# ARM_EURO_Platine3.net
KiCad netlist of a schematic drawn in Altium Designer
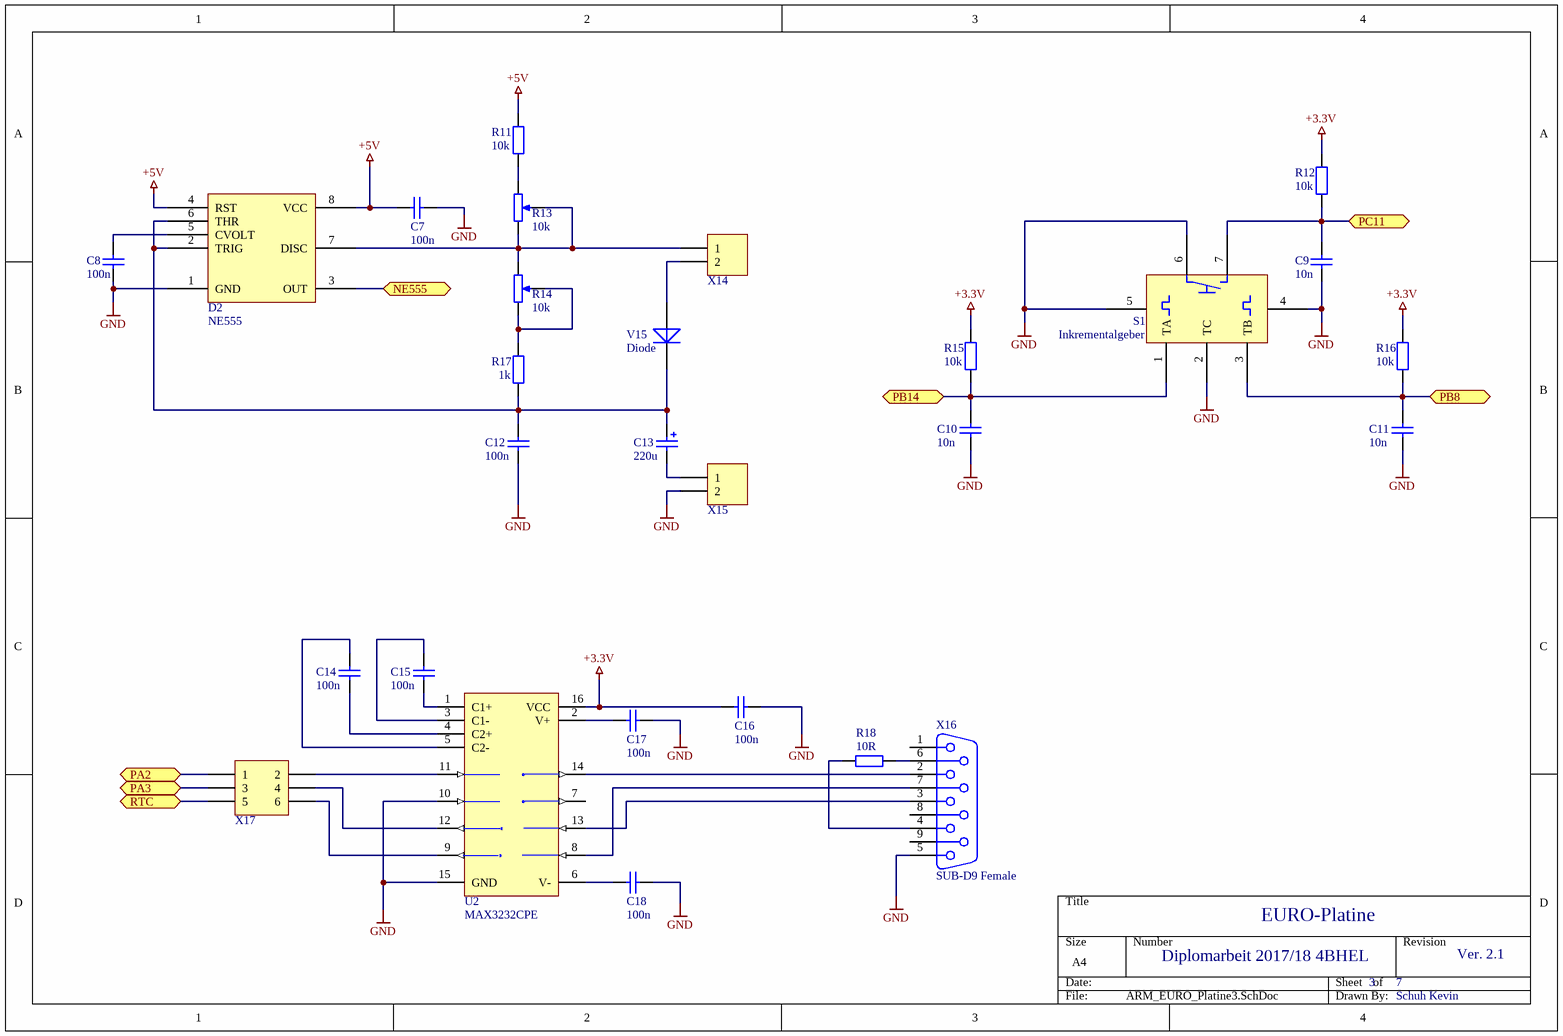
[diagram p0: ARM_EURO_Platine3.SchDoc]

(export (version "E")
  (design (tool "Eeschema 10.0.6"))
  (components
    (comp (ref "C7")
      (value "100n")
      (footprint "0805_CAP")
      (description "Capacitor_SMD")
      (fields (field (name "Comment") "Cap_Keramik_SMD") (field (name "PUBLISHER") "Altium Limited"))
      (libsource (lib "ARM_Libary_EURO") (part "Cap_Keramik_SMD"))
    )
    (comp (ref "C8")
      (value "100n")
      (footprint "0805_CAP")
      (description "Capacitor_SMD")
      (fields (field (name "Comment") "Cap_Keramik_SMD") (field (name "PUBLISHER") "Altium Limited"))
      (libsource (lib "ARM_Libary_EURO") (part "Cap_Keramik_SMD"))
    )
    (comp (ref "C9")
      (value "10n")
      (footprint "0805_CAP")
      (description "Capacitor_SMD")
      (fields (field (name "Comment") "Cap_Keramik_SMD") (field (name "PUBLISHER") "Altium Limited"))
      (libsource (lib "ARM_Libary_EURO") (part "Cap_Keramik_SMD"))
    )
    (comp (ref "C10")
      (value "10n")
      (footprint "0805_CAP")
      (description "Capacitor_SMD")
      (fields (field (name "Comment") "Cap_Keramik_SMD") (field (name "PUBLISHER") "Altium Limited"))
      (libsource (lib "ARM_Libary_EURO") (part "Cap_Keramik_SMD"))
    )
    (comp (ref "C11")
      (value "10n")
      (footprint "0805_CAP")
      (description "Capacitor_SMD")
      (fields (field (name "Comment") "Cap_Keramik_SMD") (field (name "PUBLISHER") "Altium Limited"))
      (libsource (lib "ARM_Libary_EURO") (part "Cap_Keramik_SMD"))
    )
    (comp (ref "C12")
      (value "100n")
      (footprint "0805_CAP")
      (description "Capacitor_SMD")
      (fields (field (name "Comment") "Cap_Keramik_SMD") (field (name "PUBLISHER") "Altium Limited"))
      (libsource (lib "ARM_Libary_EURO") (part "Cap_Keramik_SMD"))
    )
    (comp (ref "C13")
      (value "220u")
      (footprint "100µF_16V_Kondensator")
      (description "Polarized Capacitor SMD")
      (fields (field (name "Comment") "Cap_Pol_SMD") (field (name "PUBLISHER") "Altium Limited"))
      (libsource (lib "ARM_Libary_EURO") (part "Cap_Pol_SMD"))
    )
    (comp (ref "C14")
      (value "100n")
      (footprint "0805_CAP")
      (description "Capacitor_SMD")
      (fields (field (name "Comment") "Cap_Keramik_SMD") (field (name "PUBLISHER") "Altium Limited"))
      (libsource (lib "ARM_Libary_EURO") (part "Cap_Keramik_SMD"))
    )
    (comp (ref "C15")
      (value "100n")
      (footprint "0805_CAP")
      (description "Capacitor_SMD")
      (fields (field (name "Comment") "Cap_Keramik_SMD") (field (name "PUBLISHER") "Altium Limited"))
      (libsource (lib "ARM_Libary_EURO") (part "Cap_Keramik_SMD"))
    )
    (comp (ref "C16")
      (value "100n")
      (footprint "0805_CAP")
      (description "Capacitor_SMD")
      (fields (field (name "Comment") "Cap_Keramik_SMD") (field (name "PUBLISHER") "Altium Limited"))
      (libsource (lib "ARM_Libary_EURO") (part "Cap_Keramik_SMD"))
    )
    (comp (ref "C17")
      (value "100n")
      (footprint "0805_CAP")
      (description "Capacitor_SMD")
      (fields (field (name "Comment") "Cap_Keramik_SMD") (field (name "PUBLISHER") "Altium Limited"))
      (libsource (lib "ARM_Libary_EURO") (part "Cap_Keramik_SMD"))
    )
    (comp (ref "C18")
      (value "100n")
      (footprint "0805_CAP")
      (description "Capacitor_SMD")
      (fields (field (name "Comment") "Cap_Keramik_SMD") (field (name "PUBLISHER") "Altium Limited"))
      (libsource (lib "ARM_Libary_EURO") (part "Cap_Keramik_SMD"))
    )
    (comp (ref "D2") (value "NE555") (footprint "PDIP8") (libsource (lib "ARM_Libary_EURO") (part "NE555")))
    (comp (ref "R11")
      (value "10k")
      (footprint "0805_Res")
      (description "Resistor")
      (fields (field (name "Comment") "Res_SMD") (field (name "PUBLISHER") "Altium Limited"))
      (libsource (lib "ARM_Libary_EURO") (part "Res_SMD"))
    )
    (comp (ref "R12")
      (value "10k")
      (footprint "0805_Res")
      (description "Resistor")
      (fields (field (name "Comment") "Res_SMD") (field (name "PUBLISHER") "Altium Limited"))
      (libsource (lib "ARM_Libary_EURO") (part "Res_SMD"))
    )
    (comp (ref "R13")
      (value "10k")
      (footprint "Potentiometer")
      (description "Potentiometer")
      (fields (field (name "Comment") "RPot") (field (name "PUBLISHER") "Altium Limited"))
      (libsource (lib "ARM_Libary_EURO") (part "RPot"))
    )
    (comp (ref "R14")
      (value "10k")
      (footprint "Potentiometer")
      (description "Potentiometer")
      (fields (field (name "Comment") "RPot") (field (name "PUBLISHER") "Altium Limited"))
      (libsource (lib "ARM_Libary_EURO") (part "RPot"))
    )
    (comp (ref "R15")
      (value "10k")
      (footprint "0805_Res")
      (description "Resistor")
      (fields (field (name "Comment") "Res_SMD") (field (name "PUBLISHER") "Altium Limited"))
      (libsource (lib "ARM_Libary_EURO") (part "Res_SMD"))
    )
    (comp (ref "R16")
      (value "10k")
      (footprint "0805_Res")
      (description "Resistor")
      (fields (field (name "Comment") "Res_SMD") (field (name "PUBLISHER") "Altium Limited"))
      (libsource (lib "ARM_Libary_EURO") (part "Res_SMD"))
    )
    (comp (ref "R17")
      (value "1k")
      (footprint "0805_Res")
      (description "Resistor")
      (fields (field (name "Comment") "Res_SMD") (field (name "PUBLISHER") "Altium Limited"))
      (libsource (lib "ARM_Libary_EURO") (part "Res_SMD"))
    )
    (comp (ref "R18")
      (value "10R")
      (footprint "0805_Res")
      (description "Resistor")
      (fields (field (name "Comment") "Res_SMD") (field (name "PUBLISHER") "Altium Limited"))
      (libsource (lib "") (part "Res_SMD_1"))
    )
    (comp (ref "S1")
      (value "Inkrementalgeber")
      (footprint "Inkrementalgeber")
      (libsource (lib "ARM_Libary_EURO") (part "Inkrementalgeber"))
    )
    (comp (ref "U2")
      (value "MAX3232CPE")
      (footprint "DIP_16")
      (description "3.0V TO 5.5V, Low-Power, up to 1Mbps, True RS-232 Transceiver Using Four 0.1µF External Capacitor")
      (fields (field (name "PUBLISHER") "Altium Limited"))
      (libsource (lib "ARM_Libary_EURO") (part "MAX3232CPE"))
    )
    (comp (ref "V15")
      (value "Diode")
      (footprint "Diode")
      (description "Schottky Diode")
      (fields (field (name "PUBLISHER") "Altium Limited"))
      (libsource (lib "ARM_Libary_EURO") (part "Diode"))
    )
    (comp (ref "X14")
      (value "Header")
      (footprint "HDR1X2")
      (description "Header, 2-Pin")
      (fields (field (name "PUBLISHER") "Altium Limited"))
      (libsource (lib "ARM_Libary_EURO") (part "Header_2"))
    )
    (comp (ref "X15")
      (value "Header")
      (footprint "HDR1X2")
      (description "Header, 2-Pin")
      (fields (field (name "PUBLISHER") "Altium Limited"))
      (libsource (lib "ARM_Libary_EURO") (part "Header_2"))
    )
    (comp (ref "X16")
      (value "SUB-D9 Female")
      (footprint "SUBD_9")
      (fields (field (name "PUBLISHER") "Altium Limited"))
      (libsource (lib "ARM_Libary_EURO") (part "SUB_D9"))
    )
    (comp (ref "X17")
      (value "Header_3x2")
      (footprint "HDR2X3")
      (description "Header, 3x2-Pin")
      (fields (field (name "PUBLISHER") "Altium Limited"))
      (libsource (lib "ARM_Libary_EURO") (part "Header_3x2"))
    )
  )
  (nets
    (net (code "1") (name "+3.3V") (class "Default")
      (node (ref "C16") (pin "1") (pinfunction "1_1") (pintype "passive"))
      (node (ref "R12") (pin "1") (pinfunction "1_1") (pintype "passive"))
      (node (ref "R15") (pin "1") (pinfunction "1_1") (pintype "passive"))
      (node (ref "R16") (pin "1") (pinfunction "1_1") (pintype "passive"))
      (node (ref "U2") (pin "16") (pinfunction "VCC_16") (pintype "power_in"))
    )
    (net (code "2") (name "+5V") (class "Default")
      (node (ref "C7") (pin "2") (pinfunction "2_2") (pintype "passive"))
      (node (ref "D2") (pin "4") (pinfunction "RST_4") (pintype "passive"))
      (node (ref "D2") (pin "8") (pinfunction "VCC_8") (pintype "passive"))
      (node (ref "R11") (pin "1") (pinfunction "1_1") (pintype "passive"))
    )
    (net (code "3") (name "/NE555") (class "Default")
      (node (ref "D2") (pin "3") (pinfunction "OUT_3") (pintype "passive"))
    )
    (net (code "4") (name "/PA2") (class "Default")
      (node (ref "X17") (pin "1") (pinfunction "1_1") (pintype "passive"))
    )
    (net (code "5") (name "/PA3") (class "Default")
      (node (ref "X17") (pin "3") (pinfunction "3_3") (pintype "passive"))
    )
    (net (code "6") (name "/PB8") (class "Default")
      (node (ref "C11") (pin "1") (pinfunction "1_1") (pintype "passive"))
      (node (ref "R16") (pin "2") (pinfunction "2_2") (pintype "passive"))
      (node (ref "S1") (pin "3") (pinfunction "TB_3") (pintype "passive"))
    )
    (net (code "7") (name "/PB14") (class "Default")
      (node (ref "C10") (pin "1") (pinfunction "1_1") (pintype "passive"))
      (node (ref "R15") (pin "2") (pinfunction "2_2") (pintype "passive"))
      (node (ref "S1") (pin "1") (pinfunction "TA_1") (pintype "passive"))
    )
    (net (code "8") (name "/PC11") (class "Default")
      (node (ref "C9") (pin "1") (pinfunction "1_1") (pintype "passive"))
      (node (ref "R12") (pin "2") (pinfunction "2_2") (pintype "passive"))
      (node (ref "S1") (pin "7") (pinfunction "7_7") (pintype "passive"))
    )
    (net (code "9") (name "/RTC") (class "Default")
      (node (ref "X17") (pin "5") (pinfunction "5_5") (pintype "passive"))
    )
    (net (code "10") (name "GND") (class "Default")
      (node (ref "C10") (pin "2") (pinfunction "2_2") (pintype "passive"))
      (node (ref "C11") (pin "2") (pinfunction "2_2") (pintype "passive"))
      (node (ref "C12") (pin "2") (pinfunction "2_2") (pintype "passive"))
      (node (ref "C16") (pin "2") (pinfunction "2_2") (pintype "passive"))
      (node (ref "C17") (pin "2") (pinfunction "2_2") (pintype "passive"))
      (node (ref "C18") (pin "2") (pinfunction "2_2") (pintype "passive"))
      (node (ref "C7") (pin "1") (pinfunction "1_1") (pintype "passive"))
      (node (ref "C8") (pin "2") (pinfunction "2_2") (pintype "passive"))
      (node (ref "C9") (pin "2") (pinfunction "2_2") (pintype "passive"))
      (node (ref "D2") (pin "1") (pinfunction "GND_1") (pintype "passive"))
      (node (ref "S1") (pin "2") (pinfunction "TC_2") (pintype "passive"))
      (node (ref "S1") (pin "4") (pinfunction "4_4") (pintype "passive"))
      (node (ref "S1") (pin "5") (pinfunction "5_5") (pintype "passive"))
      (node (ref "S1") (pin "6") (pinfunction "6_6") (pintype "passive"))
      (node (ref "U2") (pin "10") (pinfunction "T2IN_10") (pintype "input"))
      (node (ref "U2") (pin "15") (pinfunction "GND_15") (pintype "power_in"))
      (node (ref "X15") (pin "2") (pinfunction "2_2") (pintype "passive"))
      (node (ref "X16") (pin "5") (pinfunction "5_5") (pintype "passive"))
    )
    (net (code "11") (name "Net-(C13-Pad2)") (class "Default")
      (node (ref "C13") (pin "2") (pinfunction "2_2") (pintype "passive"))
      (node (ref "X15") (pin "1") (pinfunction "1_1") (pintype "passive"))
    )
    (net (code "12") (name "Net-(D2-CVOLT)") (class "Default")
      (node (ref "C8") (pin "1") (pinfunction "1_1") (pintype "passive"))
      (node (ref "D2") (pin "5") (pinfunction "CVOLT_5") (pintype "passive"))
    )
    (net (code "13") (name "Net-(D2-DISC)") (class "Default")
      (node (ref "D2") (pin "7") (pinfunction "DISC_7") (pintype "passive"))
      (node (ref "R13") (pin "2") (pinfunction "BOT_2") (pintype "passive"))
      (node (ref "R13") (pin "3") (pinfunction "TAP_3") (pintype "passive"))
      (node (ref "R14") (pin "1") (pinfunction "TOP_1") (pintype "passive"))
      (node (ref "X14") (pin "1") (pinfunction "1_1") (pintype "passive"))
    )
    (net (code "14") (name "Net-(D2-THR)") (class "Default")
      (node (ref "C12") (pin "1") (pinfunction "1_1") (pintype "passive"))
      (node (ref "C13") (pin "1") (pinfunction "1_1") (pintype "passive"))
      (node (ref "D2") (pin "2") (pinfunction "TRIG_2") (pintype "passive"))
      (node (ref "D2") (pin "6") (pinfunction "THR_6") (pintype "passive"))
      (node (ref "R17") (pin "2") (pinfunction "2_2") (pintype "passive"))
      (node (ref "V15") (pin "2") (pinfunction "K_2") (pintype "passive"))
    )
    (net (code "15") (name "Net-(R13-TOP)") (class "Default")
      (node (ref "R11") (pin "2") (pinfunction "2_2") (pintype "passive"))
      (node (ref "R13") (pin "1") (pinfunction "TOP_1") (pintype "passive"))
    )
    (net (code "16") (name "Net-(R14-BOT)") (class "Default")
      (node (ref "R14") (pin "2") (pinfunction "BOT_2") (pintype "passive"))
      (node (ref "R14") (pin "3") (pinfunction "TAP_3") (pintype "passive"))
      (node (ref "R17") (pin "1") (pinfunction "1_1") (pintype "passive"))
    )
    (net (code "17") (name "Net-(R18-Pad1)") (class "Default")
      (node (ref "R18") (pin "1") (pinfunction "1_1") (pintype "passive"))
      (node (ref "X16") (pin "4") (pinfunction "4_4") (pintype "passive"))
    )
    (net (code "18") (name "Net-(R18-Pad2)") (class "Default")
      (node (ref "R18") (pin "2") (pinfunction "2_2") (pintype "passive"))
      (node (ref "X16") (pin "6") (pinfunction "6_6") (pintype "passive"))
    )
    (net (code "19") (name "Net-(U2-C1+)") (class "Default")
      (node (ref "C15") (pin "1") (pinfunction "1_1") (pintype "passive"))
      (node (ref "U2") (pin "1") (pinfunction "C1+_1") (pintype "passive"))
    )
    (net (code "20") (name "Net-(U2-C1-)") (class "Default")
      (node (ref "C15") (pin "2") (pinfunction "2_2") (pintype "passive"))
      (node (ref "U2") (pin "3") (pinfunction "C1-_3") (pintype "passive"))
    )
    (net (code "21") (name "Net-(U2-C2+)") (class "Default")
      (node (ref "C14") (pin "1") (pinfunction "1_1") (pintype "passive"))
      (node (ref "U2") (pin "4") (pinfunction "C2+_4") (pintype "passive"))
    )
    (net (code "22") (name "Net-(U2-C2-)") (class "Default")
      (node (ref "C14") (pin "2") (pinfunction "2_2") (pintype "passive"))
      (node (ref "U2") (pin "5") (pinfunction "C2-_5") (pintype "passive"))
    )
    (net (code "23") (name "Net-(U2-R1IN)") (class "Default")
      (node (ref "U2") (pin "13") (pinfunction "R1IN_13") (pintype "input"))
      (node (ref "X16") (pin "3") (pinfunction "3_3") (pintype "passive"))
    )
    (net (code "24") (name "Net-(U2-R1OUT)") (class "Default")
      (node (ref "U2") (pin "12") (pinfunction "R1OUT_12") (pintype "output"))
      (node (ref "X17") (pin "4") (pinfunction "4_4") (pintype "passive"))
    )
    (net (code "25") (name "Net-(U2-R2IN)") (class "Default")
      (node (ref "U2") (pin "8") (pinfunction "R2IN_8") (pintype "input"))
      (node (ref "X16") (pin "7") (pinfunction "7_7") (pintype "passive"))
    )
    (net (code "26") (name "Net-(U2-R2OUT)") (class "Default")
      (node (ref "U2") (pin "9") (pinfunction "R2OUT_9") (pintype "output"))
      (node (ref "X17") (pin "6") (pinfunction "6_6") (pintype "passive"))
    )
    (net (code "27") (name "Net-(U2-T1IN)") (class "Default")
      (node (ref "U2") (pin "11") (pinfunction "T1IN_11") (pintype "input"))
      (node (ref "X17") (pin "2") (pinfunction "2_2") (pintype "passive"))
    )
    (net (code "28") (name "Net-(U2-T1OUT)") (class "Default")
      (node (ref "U2") (pin "14") (pinfunction "T1OUT_14") (pintype "output"))
      (node (ref "X16") (pin "2") (pinfunction "2_2") (pintype "passive"))
    )
    (net (code "29") (name "Net-(U2-V+)") (class "Default")
      (node (ref "C17") (pin "1") (pinfunction "1_1") (pintype "passive"))
      (node (ref "U2") (pin "2") (pinfunction "V+_2") (pintype "power_in"))
    )
    (net (code "30") (name "Net-(U2-V-)") (class "Default")
      (node (ref "C18") (pin "1") (pinfunction "1_1") (pintype "passive"))
      (node (ref "U2") (pin "6") (pinfunction "V-_6") (pintype "power_in"))
    )
    (net (code "31") (name "Net-(V15-A)") (class "Default")
      (node (ref "V15") (pin "1") (pinfunction "A_1") (pintype "passive"))
      (node (ref "X14") (pin "2") (pinfunction "2_2") (pintype "passive"))
    )
    (net (code "32") (name "unconnected-(U2-T2OUT-Pad7)") (class "Default")
      (node (ref "U2") (pin "7") (pinfunction "T2OUT_7") (pintype "output"))
    )
    (net (code "33") (name "unconnected-(X16-Pad1)") (class "Default")
      (node (ref "X16") (pin "1") (pinfunction "1_1") (pintype "passive"))
    )
    (net (code "34") (name "unconnected-(X16-Pad8)") (class "Default")
      (node (ref "X16") (pin "8") (pinfunction "8_8") (pintype "passive"))
    )
    (net (code "35") (name "unconnected-(X16-Pad9)") (class "Default")
      (node (ref "X16") (pin "9") (pinfunction "9_9") (pintype "passive"))
    )
  )
)
